# GERI_Gadget.net
KiCad netlist of a schematic drawn in EAGLE
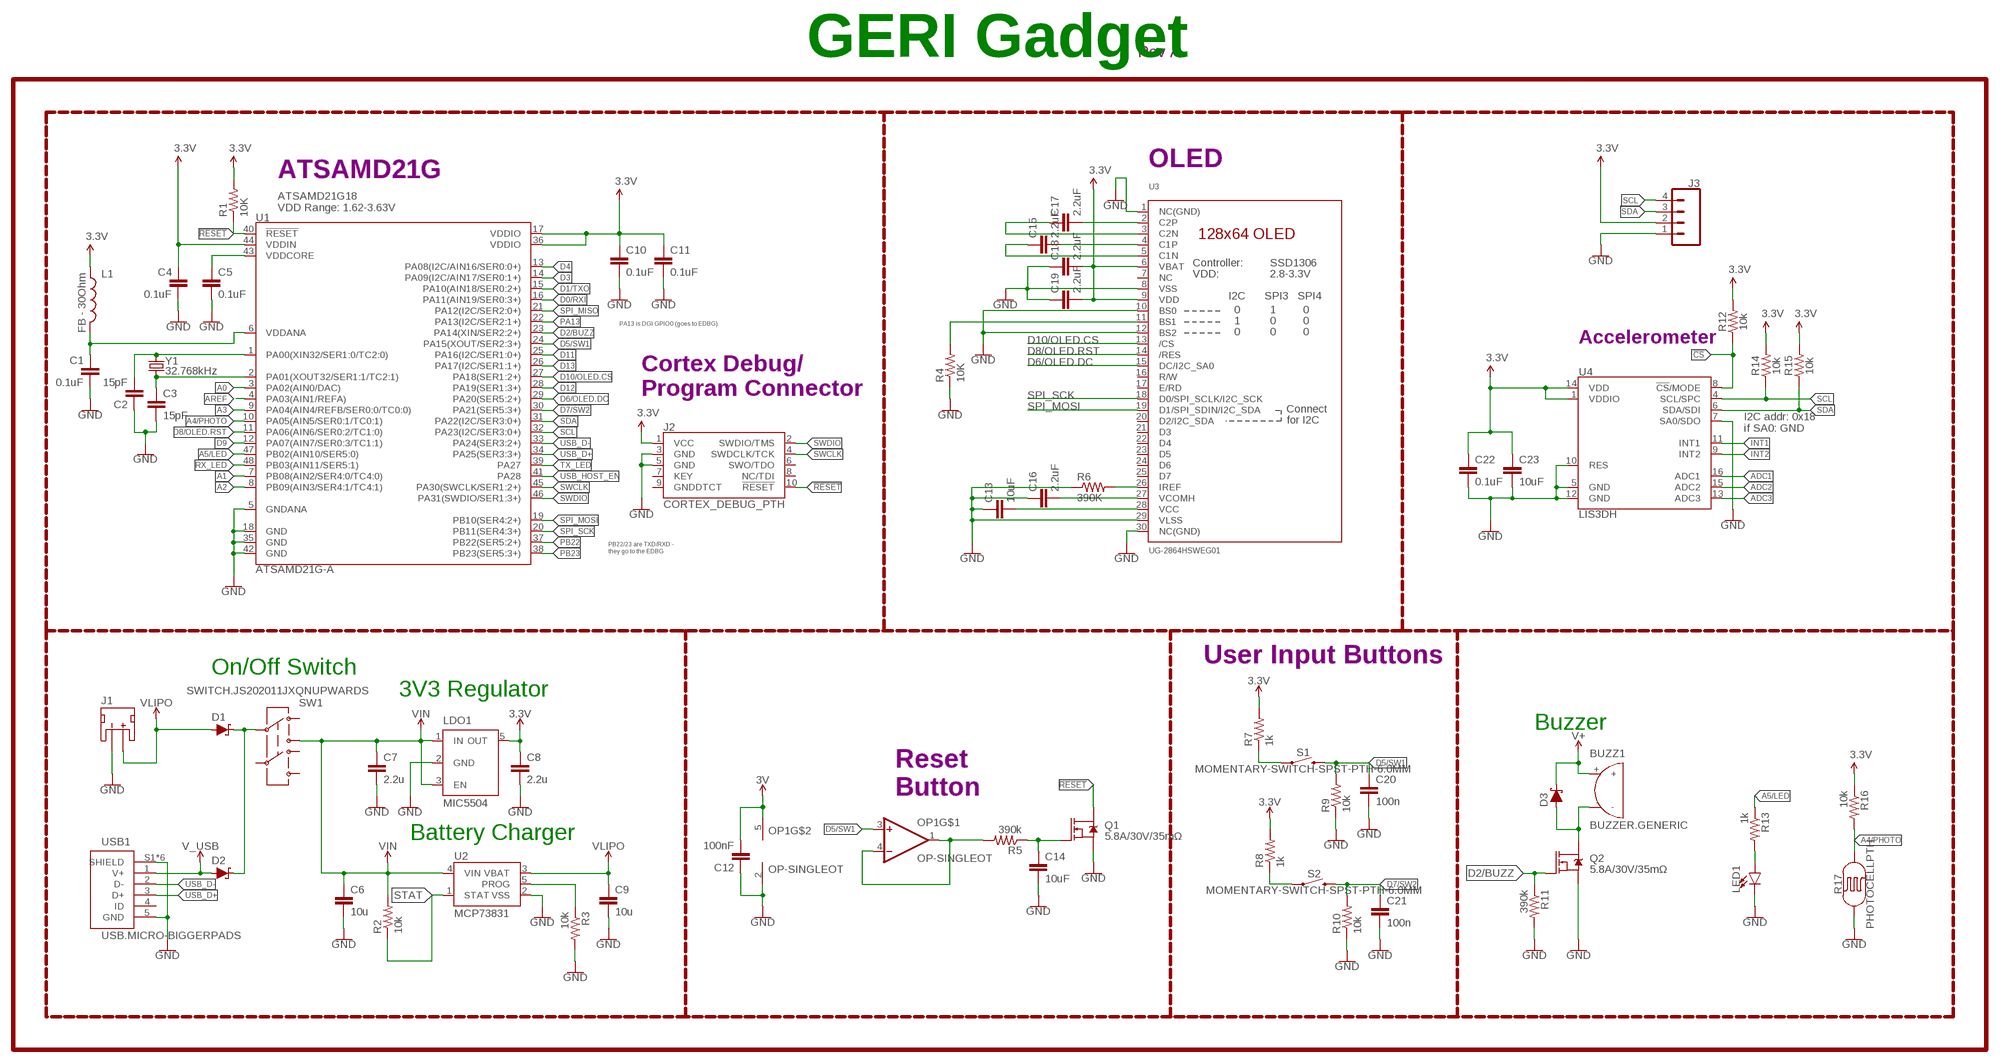
[diagram p0: schematic, sheet 1]

(export (version "E")
  (design (tool "Eeschema 10.0.6"))
  (components
    (comp (ref "BUZZ1")
      (value "BUZZER.GENERIC")
      (footprint "eagle-import:PIEZO-1")
      (libsource (lib "eagle-import") (part "BUZZER.GENERIC"))
    )
    (comp (ref "C1")
      (value "0.1uF")
      (footprint "eagle-import:C0402")
      (libsource (lib "eagle-import") (part "CAPACITOR0402"))
    )
    (comp (ref "C2")
      (value "15pF")
      (footprint "eagle-import:C0402")
      (libsource (lib "eagle-import") (part "CAPACITOR0402"))
    )
    (comp (ref "C3")
      (value "15pF")
      (footprint "eagle-import:C0402")
      (libsource (lib "eagle-import") (part "CAPACITOR0402"))
    )
    (comp (ref "C4")
      (value "0.1uF")
      (footprint "eagle-import:C0402")
      (libsource (lib "eagle-import") (part "CAPACITOR0402"))
    )
    (comp (ref "C5")
      (value "0.1uF")
      (footprint "eagle-import:C0402")
      (libsource (lib "eagle-import") (part "CAPACITOR0402"))
    )
    (comp (ref "C6")
      (value "10u")
      (footprint "eagle-import:C0603")
      (libsource (lib "eagle-import") (part "CAPACITOR0603"))
    )
    (comp (ref "C7")
      (value "2.2u")
      (footprint "eagle-import:C0603")
      (libsource (lib "eagle-import") (part "CAPACITOR0603"))
    )
    (comp (ref "C8")
      (value "2.2u")
      (footprint "eagle-import:C0603")
      (libsource (lib "eagle-import") (part "CAPACITOR0603"))
    )
    (comp (ref "C9")
      (value "10u")
      (footprint "eagle-import:C0603")
      (libsource (lib "eagle-import") (part "CAPACITOR0603"))
    )
    (comp (ref "C10")
      (value "0.1uF")
      (footprint "eagle-import:C0402")
      (libsource (lib "eagle-import") (part "CAPACITOR0402"))
    )
    (comp (ref "C11")
      (value "0.1uF")
      (footprint "eagle-import:C0402")
      (libsource (lib "eagle-import") (part "CAPACITOR0402"))
    )
    (comp (ref "C12")
      (value "100nF")
      (footprint "eagle-import:C0402")
      (libsource (lib "eagle-import") (part "CAPACITOR0402"))
    )
    (comp (ref "C13")
      (value "10uF")
      (footprint "eagle-import:C0603")
      (libsource (lib "eagle-import") (part "CAPACITOR0603"))
    )
    (comp (ref "C14")
      (value "10uF")
      (footprint "eagle-import:C0603")
      (libsource (lib "eagle-import") (part "CAPACITOR0603"))
    )
    (comp (ref "C15")
      (value "2.2uF")
      (footprint "eagle-import:C0603")
      (libsource (lib "eagle-import") (part "CAPACITOR0603"))
    )
    (comp (ref "C16")
      (value "2.2uF")
      (footprint "eagle-import:C0603")
      (libsource (lib "eagle-import") (part "CAPACITOR0603"))
    )
    (comp (ref "C17")
      (value "2.2uF")
      (footprint "eagle-import:C0603")
      (libsource (lib "eagle-import") (part "CAPACITOR0603"))
    )
    (comp (ref "C18")
      (value "2.2uF")
      (footprint "eagle-import:C0603")
      (libsource (lib "eagle-import") (part "CAPACITOR0603"))
    )
    (comp (ref "C19")
      (value "2.2uF")
      (footprint "eagle-import:C0603")
      (libsource (lib "eagle-import") (part "CAPACITOR0603"))
    )
    (comp (ref "C20")
      (value "100n")
      (footprint "eagle-import:C0402")
      (libsource (lib "eagle-import") (part "CAPACITOR0402"))
    )
    (comp (ref "C21")
      (value "100n")
      (footprint "eagle-import:C0402")
      (libsource (lib "eagle-import") (part "CAPACITOR0402"))
    )
    (comp (ref "C22")
      (value "0.1uF")
      (footprint "eagle-import:0402")
      (libsource (lib "eagle-import") (part "0.1UF-0402-16V-10%"))
    )
    (comp (ref "C23")
      (value "10uF")
      (footprint "eagle-import:0603")
      (libsource (lib "eagle-import") (part "10UF-0603-6.3V-20%"))
    )
    (comp (ref "D1")
      (value "SCHOTTKY-USC")
      (footprint "eagle-import:USC")
      (libsource (lib "eagle-import") (part "SCHOTTKY-USC"))
    )
    (comp (ref "D2")
      (value "SCHOTTKY-USC")
      (footprint "eagle-import:USC")
      (libsource (lib "eagle-import") (part "SCHOTTKY-USC"))
    )
    (comp (ref "D3")
      (value "SCHOTTKY-USC")
      (footprint "eagle-import:USC")
      (libsource (lib "eagle-import") (part "SCHOTTKY-USC"))
    )
    (comp (ref "J1")
      (value "JST_2MM_MALE")
      (footprint "eagle-import:JST-2-SMD")
      (libsource (lib "eagle-import") (part "JST_2MM_MALE"))
    )
    (comp (ref "J2")
      (value "CORTEX_DEBUG_PTH")
      (footprint "eagle-import:2X5-PTH-1.27MM")
      (libsource (lib "eagle-import") (part "CORTEX_DEBUG_PTH"))
    )
    (comp (ref "J3")
      (value "CONN_04")
      (footprint "eagle-import:1X04")
      (libsource (lib "eagle-import") (part "CONN_04"))
    )
    (comp (ref "L1")
      (value "FB - 30Ohm")
      (footprint "eagle-import:0603")
      (libsource (lib "eagle-import") (part "INDUCTOR0603"))
    )
    (comp (ref "LDO1")
      (value "MIC5504")
      (footprint "eagle-import:SOT23-5")
      (libsource (lib "eagle-import") (part "MIC5504"))
    )
    (comp (ref "LED1")
      (value "LED5MM")
      (footprint "eagle-import:LED_5MM")
      (libsource (lib "eagle-import") (part "LED5MM"))
    )
    (comp (ref "OP1")
      (value "OP-SINGLEOT")
      (footprint "eagle-import:SOT23-5")
      (libsource (lib "eagle-import") (part "OP-SINGLEOT"))
    )
    (comp (ref "Q1")
      (value "5.8A/30V/35mΩ")
      (footprint "eagle-import:SOT23-3")
      (libsource (lib "eagle-import") (part "NFET-AO3404A"))
    )
    (comp (ref "Q2")
      (value "5.8A/30V/35mΩ")
      (footprint "eagle-import:SOT23-3")
      (libsource (lib "eagle-import") (part "NFET-AO3404A"))
    )
    (comp (ref "R1")
      (value "10K")
      (footprint "eagle-import:R0402-BIGGER")
      (libsource (lib "eagle-import") (part "RESISTOR0402-BIGGER"))
    )
    (comp (ref "R2")
      (value "10k")
      (footprint "eagle-import:R0402-BIGGER")
      (libsource (lib "eagle-import") (part "RESISTOR0402-BIGGER"))
    )
    (comp (ref "R3")
      (value "10k")
      (footprint "eagle-import:R0402-BIGGER")
      (libsource (lib "eagle-import") (part "RESISTOR0402-BIGGER"))
    )
    (comp (ref "R4")
      (value "10K")
      (footprint "eagle-import:R0402-BIGGER")
      (libsource (lib "eagle-import") (part "RESISTOR0402-BIGGER"))
    )
    (comp (ref "R5")
      (value "390k")
      (footprint "eagle-import:R0402-BIGGER")
      (libsource (lib "eagle-import") (part "RESISTOR0402-BIGGER"))
    )
    (comp (ref "R6")
      (value "390K")
      (footprint "eagle-import:R0402-BIGGER")
      (libsource (lib "eagle-import") (part "RESISTOR0402-BIGGER"))
    )
    (comp (ref "R7")
      (value "1k")
      (footprint "eagle-import:R0402-BIGGER")
      (libsource (lib "eagle-import") (part "RESISTOR0402-BIGGER"))
    )
    (comp (ref "R8")
      (value "1k")
      (footprint "eagle-import:R0402-BIGGER")
      (libsource (lib "eagle-import") (part "RESISTOR0402-BIGGER"))
    )
    (comp (ref "R9")
      (value "10k")
      (footprint "eagle-import:R0402-BIGGER")
      (libsource (lib "eagle-import") (part "RESISTOR0402-BIGGER"))
    )
    (comp (ref "R10")
      (value "10k")
      (footprint "eagle-import:R0402-BIGGER")
      (libsource (lib "eagle-import") (part "RESISTOR0402-BIGGER"))
    )
    (comp (ref "R11")
      (value "390k")
      (footprint "eagle-import:R0402-BIGGER")
      (libsource (lib "eagle-import") (part "RESISTOR0402-BIGGER"))
    )
    (comp (ref "R12")
      (value "10k")
      (footprint "eagle-import:0402")
      (libsource (lib "eagle-import") (part "RESISTOR0402"))
    )
    (comp (ref "R13")
      (value "1k")
      (footprint "eagle-import:R0402-BIGGER")
      (libsource (lib "eagle-import") (part "RESISTOR0402-BIGGER"))
    )
    (comp (ref "R14")
      (value "10k")
      (footprint "eagle-import:0402")
      (libsource (lib "eagle-import") (part "RESISTOR0402"))
    )
    (comp (ref "R15")
      (value "10k")
      (footprint "eagle-import:0402")
      (libsource (lib "eagle-import") (part "RESISTOR0402"))
    )
    (comp (ref "R16")
      (value "10k")
      (footprint "eagle-import:R0402-BIGGER")
      (libsource (lib "eagle-import") (part "RESISTOR0402-BIGGER"))
    )
    (comp (ref "R17")
      (value "PHOTOCELLPTH")
      (footprint "eagle-import:PHOTOCELL")
      (libsource (lib "eagle-import") (part "PHOTOCELLPTH"))
    )
    (comp (ref "REV1")
      (value "REVISION.A")
      (footprint "eagle-import:REV.A")
      (libsource (lib "eagle-import") (part "REVISION.A"))
    )
    (comp (ref "S1")
      (value "MOMENTARY-SWITCH-SPST-PTH-6.0MM")
      (footprint "eagle-import:TACTILE_SWITCH_PTH_6.0MM")
      (libsource (lib "eagle-import") (part "MOMENTARY-SWITCH-SPST-PTH-6.0MM"))
    )
    (comp (ref "S2")
      (value "MOMENTARY-SWITCH-SPST-PTH-6.0MM")
      (footprint "eagle-import:TACTILE_SWITCH_PTH_6.0MM")
      (libsource (lib "eagle-import") (part "MOMENTARY-SWITCH-SPST-PTH-6.0MM"))
    )
    (comp (ref "SW1")
      (value "SWITCH.JS202011JXQNUPWARDS")
      (footprint "eagle-import:SWITCH.00")
      (libsource (lib "eagle-import") (part "SWITCH.JS202011JXQNUPWARDS"))
    )
    (comp (ref "U1")
      (value "ATSAMD21G-A")
      (footprint "eagle-import:TQFP-48")
      (libsource (lib "eagle-import") (part "ATSAMD21G-A"))
    )
    (comp (ref "U2")
      (value "MCP73831")
      (footprint "eagle-import:SOT23-5")
      (libsource (lib "eagle-import") (part "MCP73831"))
    )
    (comp (ref "U3")
      (value "UG-2864HSWEG01")
      (footprint "eagle-import:UG-2864HSWEG01_0.96IN_NO-WRAPAROUND")
      (libsource (lib "eagle-import") (part "DISP_OLED_UG-2864HSWEG01-NO-WRAPAROUND"))
    )
    (comp (ref "U4")
      (value "LIS3DH")
      (footprint "eagle-import:LGA-16-3X3")
      (libsource (lib "eagle-import") (part "LIS3DH"))
    )
    (comp (ref "USB1")
      (value "USB.MICRO-BIGGERPADS")
      (footprint "eagle-import:USB-MICRO-01.BIGGERPADS")
      (libsource (lib "eagle-import") (part "USB.MICRO-BIGGERPADS"))
    )
    (comp (ref "Y1")
      (value "32.768kHz")
      (footprint "eagle-import:CRYSTAL-SMD-3.2X1.5MM")
      (libsource (lib "eagle-import") (part "CRYSTAL3.2X1.5MM"))
    )
  )
  (nets
    (net (code "1") (name "/~{CS}") (class "Default")
      (node (ref "R12") (pin "1") (pinfunction "1_1") (pintype "passive"))
      (node (ref "U4") (pin "8") (pinfunction "~{CS}/MODE_8") (pintype "bidirectional"))
    )
    (net (code "2") (name "/~{RESET}") (class "Default")
      (node (ref "J2") (pin "10") (pinfunction "~{RESET}_10") (pintype "bidirectional"))
      (node (ref "Q1") (pin "3") (pinfunction "D_3") (pintype "bidirectional"))
      (node (ref "R1") (pin "1") (pinfunction "1_1") (pintype "passive"))
      (node (ref "U1") (pin "40") (pinfunction "~{RESET}_40") (pintype "bidirectional"))
    )
    (net (code "3") (name "3.3V") (class "Default")
      (node (ref "C10") (pin "1") (pinfunction "1_1") (pintype "passive"))
      (node (ref "C11") (pin "1") (pinfunction "1_1") (pintype "passive"))
      (node (ref "C18") (pin "2") (pinfunction "2_2") (pintype "passive"))
      (node (ref "C19") (pin "2") (pinfunction "2_2") (pintype "passive"))
      (node (ref "C22") (pin "1") (pinfunction "1_1") (pintype "passive"))
      (node (ref "C23") (pin "1") (pinfunction "1_1") (pintype "passive"))
      (node (ref "C4") (pin "1") (pinfunction "1_1") (pintype "passive"))
      (node (ref "C8") (pin "1") (pinfunction "1_1") (pintype "passive"))
      (node (ref "J2") (pin "1") (pinfunction "VCC_1") (pintype "bidirectional"))
      (node (ref "J3") (pin "2") (pinfunction "2_2") (pintype "passive"))
      (node (ref "L1") (pin "1") (pinfunction "1_1") (pintype "passive"))
      (node (ref "LDO1") (pin "5") (pinfunction "OUT_5") (pintype "bidirectional"))
      (node (ref "R1") (pin "2") (pinfunction "2_2") (pintype "passive"))
      (node (ref "R12") (pin "2") (pinfunction "2_2") (pintype "passive"))
      (node (ref "R14") (pin "2") (pinfunction "2_2") (pintype "passive"))
      (node (ref "R15") (pin "2") (pinfunction "2_2") (pintype "passive"))
      (node (ref "R16") (pin "1") (pinfunction "1_1") (pintype "passive"))
      (node (ref "R7") (pin "2") (pinfunction "2_2") (pintype "passive"))
      (node (ref "R8") (pin "2") (pinfunction "2_2") (pintype "passive"))
      (node (ref "U1") (pin "17") (pinfunction "VDDIO_17") (pintype "bidirectional"))
      (node (ref "U1") (pin "36") (pinfunction "VDDIO_36") (pintype "bidirectional"))
      (node (ref "U1") (pin "44") (pinfunction "VDDIN_44") (pintype "bidirectional"))
      (node (ref "U3") (pin "6") (pinfunction "VBAT_6") (pintype "input"))
      (node (ref "U3") (pin "9") (pinfunction "VDD_9") (pintype "power_in"))
      (node (ref "U4") (pin "1") (pinfunction "VDDIO_1") (pintype "bidirectional"))
      (node (ref "U4") (pin "14") (pinfunction "VDD_14") (pintype "bidirectional"))
    )
    (net (code "4") (name "3V") (class "Default")
      (node (ref "C12") (pin "2") (pinfunction "2_2") (pintype "passive"))
      (node (ref "OP1") (pin "5") (pinfunction "V+_5") (pintype "power_in"))
    )
    (net (code "5") (name "A0") (class "Default")
      (node (ref "U1") (pin "3") (pinfunction "PA02(AIN0/DAC)_3") (pintype "bidirectional"))
    )
    (net (code "6") (name "A1") (class "Default")
      (node (ref "U1") (pin "7") (pinfunction "PB08(AIN2/SER4:0/TC4:0)_7") (pintype "bidirectional"))
    )
    (net (code "7") (name "A2") (class "Default")
      (node (ref "U1") (pin "8") (pinfunction "PB09(AIN3/SER4:1/TC4:1)_8") (pintype "bidirectional"))
    )
    (net (code "8") (name "A3") (class "Default")
      (node (ref "U1") (pin "9") (pinfunction "PA04(AIN4/REFB/SER0:0/TC0:0)_9") (pintype "bidirectional"))
    )
    (net (code "9") (name "A4{slash}PHOTO") (class "Default")
      (node (ref "R16") (pin "2") (pinfunction "2_2") (pintype "passive"))
      (node (ref "R17") (pin "2") (pinfunction "P$2_2") (pintype "bidirectional"))
      (node (ref "U1") (pin "10") (pinfunction "PA05(AIN5/SER0:1/TC0:1)_10") (pintype "bidirectional"))
    )
    (net (code "10") (name "A5{slash}LED") (class "Default")
      (node (ref "R13") (pin "1") (pinfunction "1_1") (pintype "passive"))
      (node (ref "U1") (pin "47") (pinfunction "PB02(AIN10/SER5:0)_47") (pintype "bidirectional"))
    )
    (net (code "11") (name "ADC1") (class "Default")
      (node (ref "U4") (pin "16") (pinfunction "ADC1_16") (pintype "bidirectional"))
    )
    (net (code "12") (name "ADC2") (class "Default")
      (node (ref "U4") (pin "15") (pinfunction "ADC2_15") (pintype "bidirectional"))
    )
    (net (code "13") (name "ADC3") (class "Default")
      (node (ref "U4") (pin "13") (pinfunction "ADC3_13") (pintype "bidirectional"))
    )
    (net (code "14") (name "AREF") (class "Default")
      (node (ref "U1") (pin "4") (pinfunction "PA03(AIN1/REFA)_4") (pintype "bidirectional"))
    )
    (net (code "15") (name "D0{slash}RXI") (class "Default")
      (node (ref "U1") (pin "16") (pinfunction "PA11(AIN19/SER0:3+)_16") (pintype "bidirectional"))
    )
    (net (code "16") (name "D1{slash}TXO") (class "Default")
      (node (ref "U1") (pin "15") (pinfunction "PA10(AIN18/SER0:2+)_15") (pintype "bidirectional"))
    )
    (net (code "17") (name "D2{slash}BUZZ") (class "Default")
      (node (ref "Q2") (pin "1") (pinfunction "G_1") (pintype "bidirectional"))
      (node (ref "R11") (pin "1") (pinfunction "1_1") (pintype "passive"))
      (node (ref "U1") (pin "23") (pinfunction "PA14(XIN/SER2:2+)_23") (pintype "bidirectional"))
    )
    (net (code "18") (name "D3") (class "Default")
      (node (ref "U1") (pin "14") (pinfunction "PA09(I2C/AIN17/SER0:1+)_14") (pintype "bidirectional"))
    )
    (net (code "19") (name "D4") (class "Default")
      (node (ref "U1") (pin "13") (pinfunction "PA08(I2C/AIN16/SER0:0+)_13") (pintype "bidirectional"))
    )
    (net (code "20") (name "D5{slash}SW1") (class "Default")
      (node (ref "C20") (pin "1") (pinfunction "1_1") (pintype "passive"))
      (node (ref "OP1") (pin "3") (pinfunction "+IN_3") (pintype "input"))
      (node (ref "R9") (pin "2") (pinfunction "2_2") (pintype "passive"))
      (node (ref "S1") (pin "3") (pinfunction "2_3") (pintype "passive"))
      (node (ref "U1") (pin "24") (pinfunction "PA15(XOUT/SER2:3+)_24") (pintype "bidirectional"))
    )
    (net (code "21") (name "D6{slash}OLED.DC") (class "Default")
      (node (ref "U1") (pin "29") (pinfunction "PA20(SER5:2+)_29") (pintype "bidirectional"))
      (node (ref "U3") (pin "15") (pinfunction "DC/I2C_SA0_15") (pintype "input"))
    )
    (net (code "22") (name "D7{slash}SW2") (class "Default")
      (node (ref "C21") (pin "1") (pinfunction "1_1") (pintype "passive"))
      (node (ref "R10") (pin "2") (pinfunction "2_2") (pintype "passive"))
      (node (ref "S2") (pin "3") (pinfunction "2_3") (pintype "passive"))
      (node (ref "U1") (pin "30") (pinfunction "PA21(SER5:3+)_30") (pintype "bidirectional"))
    )
    (net (code "23") (name "D8{slash}OLED.RST") (class "Default")
      (node (ref "U1") (pin "11") (pinfunction "PA06(AIN6/SER0:2/TC1:0)_11") (pintype "bidirectional"))
      (node (ref "U3") (pin "14") (pinfunction "/RES_14") (pintype "input"))
    )
    (net (code "24") (name "D9") (class "Default")
      (node (ref "U1") (pin "12") (pinfunction "PA07(AIN7/SER0:3/TC1:1)_12") (pintype "bidirectional"))
    )
    (net (code "25") (name "D10{slash}OLED.CS") (class "Default")
      (node (ref "U1") (pin "27") (pinfunction "PA18(SER1:2+)_27") (pintype "bidirectional"))
      (node (ref "U3") (pin "13") (pinfunction "/CS_13") (pintype "input"))
    )
    (net (code "26") (name "D11") (class "Default")
      (node (ref "U1") (pin "25") (pinfunction "PA16(I2C/SER1:0+)_25") (pintype "bidirectional"))
    )
    (net (code "27") (name "D12") (class "Default")
      (node (ref "U1") (pin "28") (pinfunction "PA19(SER1:3+)_28") (pintype "bidirectional"))
    )
    (net (code "28") (name "D13") (class "Default")
      (node (ref "U1") (pin "26") (pinfunction "PA17(I2C/SER1:1+)_26") (pintype "bidirectional"))
    )
    (net (code "29") (name "GND") (class "Default")
      (node (ref "C1") (pin "2") (pinfunction "2_2") (pintype "passive"))
      (node (ref "C10") (pin "2") (pinfunction "2_2") (pintype "passive"))
      (node (ref "C11") (pin "2") (pinfunction "2_2") (pintype "passive"))
      (node (ref "C12") (pin "1") (pinfunction "1_1") (pintype "passive"))
      (node (ref "C13") (pin "1") (pinfunction "1_1") (pintype "passive"))
      (node (ref "C14") (pin "2") (pinfunction "2_2") (pintype "passive"))
      (node (ref "C16") (pin "1") (pinfunction "1_1") (pintype "passive"))
      (node (ref "C18") (pin "1") (pinfunction "1_1") (pintype "passive"))
      (node (ref "C19") (pin "1") (pinfunction "1_1") (pintype "passive"))
      (node (ref "C2") (pin "1") (pinfunction "1_1") (pintype "passive"))
      (node (ref "C20") (pin "2") (pinfunction "2_2") (pintype "passive"))
      (node (ref "C21") (pin "2") (pinfunction "2_2") (pintype "passive"))
      (node (ref "C22") (pin "2") (pinfunction "2_2") (pintype "passive"))
      (node (ref "C23") (pin "2") (pinfunction "2_2") (pintype "passive"))
      (node (ref "C3") (pin "2") (pinfunction "2_2") (pintype "passive"))
      (node (ref "C4") (pin "2") (pinfunction "2_2") (pintype "passive"))
      (node (ref "C5") (pin "2") (pinfunction "2_2") (pintype "passive"))
      (node (ref "C6") (pin "2") (pinfunction "2_2") (pintype "passive"))
      (node (ref "C7") (pin "2") (pinfunction "2_2") (pintype "passive"))
      (node (ref "C8") (pin "2") (pinfunction "2_2") (pintype "passive"))
      (node (ref "C9") (pin "2") (pinfunction "2_2") (pintype "passive"))
      (node (ref "J1") (pin "1") (pinfunction "-_1") (pintype "bidirectional"))
      (node (ref "J2") (pin "3") (pinfunction "GND_3") (pintype "bidirectional"))
      (node (ref "J2") (pin "5") (pinfunction "GND_5") (pintype "bidirectional"))
      (node (ref "J3") (pin "1") (pinfunction "1_1") (pintype "passive"))
      (node (ref "LDO1") (pin "2") (pinfunction "GND_2") (pintype "bidirectional"))
      (node (ref "LED1") (pin "K") (pinfunction "C_K") (pintype "passive"))
      (node (ref "OP1") (pin "2") (pinfunction "V-_2") (pintype "power_in"))
      (node (ref "Q1") (pin "2") (pinfunction "S_2") (pintype "bidirectional"))
      (node (ref "Q2") (pin "2") (pinfunction "S_2") (pintype "bidirectional"))
      (node (ref "R10") (pin "1") (pinfunction "1_1") (pintype "passive"))
      (node (ref "R11") (pin "2") (pinfunction "2_2") (pintype "passive"))
      (node (ref "R17") (pin "1") (pinfunction "P$1_1") (pintype "bidirectional"))
      (node (ref "R3") (pin "2") (pinfunction "2_2") (pintype "passive"))
      (node (ref "R4") (pin "1") (pinfunction "1_1") (pintype "passive"))
      (node (ref "R6") (pin "1") (pinfunction "1_1") (pintype "passive"))
      (node (ref "R9") (pin "1") (pinfunction "1_1") (pintype "passive"))
      (node (ref "U1") (pin "18") (pinfunction "GND_18") (pintype "bidirectional"))
      (node (ref "U1") (pin "35") (pinfunction "GND_35") (pintype "bidirectional"))
      (node (ref "U1") (pin "42") (pinfunction "GND_42") (pintype "bidirectional"))
      (node (ref "U1") (pin "5") (pinfunction "GNDANA_5") (pintype "bidirectional"))
      (node (ref "U2") (pin "2") (pinfunction "VSS_2") (pintype "power_in"))
      (node (ref "U3") (pin "1") (pinfunction "NC(GND)_1") (pintype "input"))
      (node (ref "U3") (pin "10") (pinfunction "BS0_10") (pintype "input"))
      (node (ref "U3") (pin "12") (pinfunction "BS2_12") (pintype "input"))
      (node (ref "U3") (pin "29") (pinfunction "VLSS_29") (pintype "power_in"))
      (node (ref "U3") (pin "30") (pinfunction "NC(GND)_30") (pintype "input"))
      (node (ref "U3") (pin "8") (pinfunction "VSS_8") (pintype "power_in"))
      (node (ref "U4") (pin "10") (pinfunction "RES_10") (pintype "bidirectional"))
      (node (ref "U4") (pin "12") (pinfunction "GND_12") (pintype "bidirectional"))
      (node (ref "U4") (pin "5") (pinfunction "GND_5") (pintype "bidirectional"))
      (node (ref "U4") (pin "7") (pinfunction "SA0/SDO_7") (pintype "bidirectional"))
      (node (ref "USB1") (pin "5") (pinfunction "GND_5") (pintype "bidirectional"))
      (node (ref "USB1") (pin "S1") (pinfunction "SHIELD_S1") (pintype "bidirectional"))
      (node (ref "USB1") (pin "S2") (pinfunction "SHIELD_S2") (pintype "bidirectional"))
      (node (ref "USB1") (pin "S3") (pinfunction "SHIELD_S3") (pintype "bidirectional"))
      (node (ref "USB1") (pin "S4") (pinfunction "SHIELD_S4") (pintype "bidirectional"))
      (node (ref "USB1") (pin "S5") (pinfunction "SHIELD_S5") (pintype "bidirectional"))
      (node (ref "USB1") (pin "S6") (pinfunction "SHIELD_S6") (pintype "bidirectional"))
    )
    (net (code "30") (name "INT1") (class "Default")
      (node (ref "U4") (pin "11") (pinfunction "INT1_11") (pintype "bidirectional"))
    )
    (net (code "31") (name "INT2") (class "Default")
      (node (ref "U4") (pin "9") (pinfunction "INT2_9") (pintype "bidirectional"))
    )
    (net (code "32") (name "Net-(D1-C)") (class "Default")
      (node (ref "D1") (pin "-") (pinfunction "C_-") (pintype "passive"))
      (node (ref "D2") (pin "-") (pinfunction "C_-") (pintype "passive"))
      (node (ref "SW1") (pin "2") (pinfunction "2_2") (pintype "bidirectional"))
    )
    (net (code "33") (name "Net-(D3-A)") (class "Default")
      (node (ref "BUZZ1") (pin "-") (pinfunction "-_-") (pintype "bidirectional"))
      (node (ref "D3") (pin "+") (pinfunction "A_+") (pintype "passive"))
      (node (ref "Q2") (pin "3") (pinfunction "D_3") (pintype "bidirectional"))
    )
    (net (code "34") (name "Net-(LED1-PadA)") (class "Default")
      (node (ref "LED1") (pin "A") (pinfunction "A_A") (pintype "passive"))
      (node (ref "R13") (pin "2") (pinfunction "2_2") (pintype "passive"))
    )
    (net (code "35") (name "Net-(OP1A--IN)") (class "Default")
      (node (ref "OP1") (pin "1") (pinfunction "OUT_1") (pintype "output"))
      (node (ref "OP1") (pin "4") (pinfunction "-IN_4") (pintype "input"))
      (node (ref "R5") (pin "2") (pinfunction "2_2") (pintype "passive"))
    )
    (net (code "36") (name "Net-(Q1-G)") (class "Default")
      (node (ref "C14") (pin "1") (pinfunction "1_1") (pintype "passive"))
      (node (ref "Q1") (pin "1") (pinfunction "G_1") (pintype "bidirectional"))
      (node (ref "R5") (pin "1") (pinfunction "1_1") (pintype "passive"))
    )
    (net (code "37") (name "Net-(R7-Pad1)") (class "Default")
      (node (ref "R7") (pin "1") (pinfunction "1_1") (pintype "passive"))
      (node (ref "S1") (pin "1") (pinfunction "1_1") (pintype "passive"))
    )
    (net (code "38") (name "Net-(R8-Pad1)") (class "Default")
      (node (ref "R8") (pin "1") (pinfunction "1_1") (pintype "passive"))
      (node (ref "S2") (pin "1") (pinfunction "1_1") (pintype "passive"))
    )
    (net (code "39") (name "Net-(U1-PA00(XIN32{slash}SER1:0{slash}TC2:0))") (class "Default")
      (node (ref "C2") (pin "2") (pinfunction "2_2") (pintype "passive"))
      (node (ref "U1") (pin "1") (pinfunction "PA00(XIN32/SER1:0/TC2:0)_1") (pintype "bidirectional"))
      (node (ref "Y1") (pin "P$2") (pinfunction "2_P$2") (pintype "passive"))
    )
    (net (code "40") (name "Net-(U1-PA01(XOUT32{slash}SER1:1{slash}TC2:1))") (class "Default")
      (node (ref "C3") (pin "1") (pinfunction "1_1") (pintype "passive"))
      (node (ref "U1") (pin "2") (pinfunction "PA01(XOUT32/SER1:1/TC2:1)_2") (pintype "bidirectional"))
      (node (ref "Y1") (pin "P$1") (pinfunction "1_P$1") (pintype "passive"))
    )
    (net (code "41") (name "Net-(U1-VDDANA)") (class "Default")
      (node (ref "C1") (pin "1") (pinfunction "1_1") (pintype "passive"))
      (node (ref "L1") (pin "2") (pinfunction "2_2") (pintype "passive"))
      (node (ref "U1") (pin "6") (pinfunction "VDDANA_6") (pintype "bidirectional"))
    )
    (net (code "42") (name "Net-(U1-VDDCORE)") (class "Default")
      (node (ref "C5") (pin "1") (pinfunction "1_1") (pintype "passive"))
      (node (ref "U1") (pin "43") (pinfunction "VDDCORE_43") (pintype "bidirectional"))
    )
    (net (code "43") (name "Net-(U2-PROG)") (class "Default")
      (node (ref "R3") (pin "1") (pinfunction "1_1") (pintype "passive"))
      (node (ref "U2") (pin "5") (pinfunction "PROG_5") (pintype "input"))
    )
    (net (code "44") (name "Net-(U3-BS1)") (class "Default")
      (node (ref "R4") (pin "2") (pinfunction "2_2") (pintype "passive"))
      (node (ref "U3") (pin "11") (pinfunction "BS1_11") (pintype "input"))
    )
    (net (code "45") (name "Net-(U3-C1N)") (class "Default")
      (node (ref "C15") (pin "1") (pinfunction "1_1") (pintype "passive"))
      (node (ref "U3") (pin "5") (pinfunction "C1N_5") (pintype "input"))
    )
    (net (code "46") (name "Net-(U3-C1P)") (class "Default")
      (node (ref "C15") (pin "2") (pinfunction "2_2") (pintype "passive"))
      (node (ref "U3") (pin "4") (pinfunction "C1P_4") (pintype "input"))
    )
    (net (code "47") (name "Net-(U3-C2N)") (class "Default")
      (node (ref "C17") (pin "1") (pinfunction "1_1") (pintype "passive"))
      (node (ref "U3") (pin "3") (pinfunction "C2N_3") (pintype "input"))
    )
    (net (code "48") (name "Net-(U3-C2P)") (class "Default")
      (node (ref "C17") (pin "2") (pinfunction "2_2") (pintype "passive"))
      (node (ref "U3") (pin "2") (pinfunction "C2P_2") (pintype "input"))
    )
    (net (code "49") (name "Net-(U3-IREF)") (class "Default")
      (node (ref "R6") (pin "2") (pinfunction "2_2") (pintype "passive"))
      (node (ref "U3") (pin "26") (pinfunction "IREF_26") (pintype "input"))
    )
    (net (code "50") (name "Net-(U3-VCC)") (class "Default")
      (node (ref "C13") (pin "2") (pinfunction "2_2") (pintype "passive"))
      (node (ref "U3") (pin "28") (pinfunction "VCC_28") (pintype "power_in"))
    )
    (net (code "51") (name "Net-(U3-VCOMH)") (class "Default")
      (node (ref "C16") (pin "2") (pinfunction "2_2") (pintype "passive"))
      (node (ref "U3") (pin "27") (pinfunction "VCOMH_27") (pintype "output"))
    )
    (net (code "52") (name "PA13") (class "Default")
      (node (ref "U1") (pin "22") (pinfunction "PA13(I2C/SER2:1+)_22") (pintype "bidirectional"))
    )
    (net (code "53") (name "PB22") (class "Default")
      (node (ref "U1") (pin "37") (pinfunction "PB22(SER5:2+)_37") (pintype "bidirectional"))
    )
    (net (code "54") (name "PB23") (class "Default")
      (node (ref "U1") (pin "38") (pinfunction "PB23(SER5:3+)_38") (pintype "bidirectional"))
    )
    (net (code "55") (name "RX_LED") (class "Default")
      (node (ref "U1") (pin "48") (pinfunction "PB03(AIN11/SER5:1)_48") (pintype "bidirectional"))
    )
    (net (code "56") (name "SCL") (class "Default")
      (node (ref "J3") (pin "4") (pinfunction "4_4") (pintype "passive"))
      (node (ref "R14") (pin "1") (pinfunction "1_1") (pintype "passive"))
      (node (ref "U1") (pin "32") (pinfunction "PA23(I2C/SER3:0+)_32") (pintype "bidirectional"))
      (node (ref "U4") (pin "4") (pinfunction "SCL/SPC_4") (pintype "bidirectional"))
    )
    (net (code "57") (name "SDA") (class "Default")
      (node (ref "J3") (pin "3") (pinfunction "3_3") (pintype "passive"))
      (node (ref "R15") (pin "1") (pinfunction "1_1") (pintype "passive"))
      (node (ref "U1") (pin "31") (pinfunction "PA22(I2C/SER3:0+)_31") (pintype "bidirectional"))
      (node (ref "U4") (pin "6") (pinfunction "SDA/SDI_6") (pintype "bidirectional"))
    )
    (net (code "58") (name "SPI_MISO") (class "Default")
      (node (ref "U1") (pin "21") (pinfunction "PA12(I2C/SER2:0+)_21") (pintype "bidirectional"))
    )
    (net (code "59") (name "SPI_MOSI") (class "Default")
      (node (ref "U1") (pin "19") (pinfunction "PB10(SER4:2+)_19") (pintype "bidirectional"))
      (node (ref "U3") (pin "19") (pinfunction "D1/SPI_SDIN/I2C_SDA_19") (pintype "bidirectional"))
    )
    (net (code "60") (name "SPI_SCK") (class "Default")
      (node (ref "U1") (pin "20") (pinfunction "PB11(SER4:3+)_20") (pintype "bidirectional"))
      (node (ref "U3") (pin "18") (pinfunction "D0/SPI_SCLK/I2C_SCK_18") (pintype "bidirectional"))
    )
    (net (code "61") (name "STAT") (class "Default")
      (node (ref "R2") (pin "1") (pinfunction "1_1") (pintype "passive"))
      (node (ref "U2") (pin "1") (pinfunction "STAT_1") (pintype "output"))
    )
    (net (code "62") (name "SWCLK") (class "Default")
      (node (ref "J2") (pin "4") (pinfunction "SWDCLK/TCK_4") (pintype "bidirectional"))
      (node (ref "U1") (pin "45") (pinfunction "PA30(SWCLK/SER1:2+)_45") (pintype "bidirectional"))
    )
    (net (code "63") (name "SWDIO") (class "Default")
      (node (ref "J2") (pin "2") (pinfunction "SWDIO/TMS_2") (pintype "bidirectional"))
      (node (ref "U1") (pin "46") (pinfunction "PA31(SWDIO/SER1:3+)_46") (pintype "bidirectional"))
    )
    (net (code "64") (name "TX_LED") (class "Default")
      (node (ref "U1") (pin "39") (pinfunction "PA27_39") (pintype "bidirectional"))
    )
    (net (code "65") (name "USB_D+") (class "Default")
      (node (ref "U1") (pin "34") (pinfunction "PA25(SER3:3+)_34") (pintype "bidirectional"))
      (node (ref "USB1") (pin "3") (pinfunction "D+_3") (pintype "bidirectional"))
    )
    (net (code "66") (name "USB_D-") (class "Default")
      (node (ref "U1") (pin "33") (pinfunction "PA24(SER3:2+)_33") (pintype "bidirectional"))
      (node (ref "USB1") (pin "2") (pinfunction "D-_2") (pintype "bidirectional"))
    )
    (net (code "67") (name "USB_HOST_EN") (class "Default")
      (node (ref "U1") (pin "41") (pinfunction "PA28_41") (pintype "bidirectional"))
    )
    (net (code "68") (name "V+") (class "Default")
      (node (ref "BUZZ1") (pin "+") (pinfunction "+_+") (pintype "bidirectional"))
      (node (ref "D3") (pin "-") (pinfunction "C_-") (pintype "passive"))
    )
    (net (code "69") (name "VIN") (class "Default")
      (node (ref "C6") (pin "1") (pinfunction "1_1") (pintype "passive"))
      (node (ref "C7") (pin "1") (pinfunction "1_1") (pintype "passive"))
      (node (ref "LDO1") (pin "1") (pinfunction "IN_1") (pintype "bidirectional"))
      (node (ref "LDO1") (pin "3") (pinfunction "EN_3") (pintype "bidirectional"))
      (node (ref "R2") (pin "2") (pinfunction "2_2") (pintype "passive"))
      (node (ref "SW1") (pin "3") (pinfunction "3_3") (pintype "bidirectional"))
      (node (ref "U2") (pin "4") (pinfunction "VIN_4") (pintype "power_in"))
    )
    (net (code "70") (name "VLIPO") (class "Default")
      (node (ref "C9") (pin "1") (pinfunction "1_1") (pintype "passive"))
      (node (ref "D1") (pin "+") (pinfunction "A_+") (pintype "passive"))
      (node (ref "J1") (pin "2") (pinfunction "+_2") (pintype "bidirectional"))
      (node (ref "U2") (pin "3") (pinfunction "VBAT_3") (pintype "power_in"))
    )
    (net (code "71") (name "V_USB") (class "Default")
      (node (ref "D2") (pin "+") (pinfunction "A_+") (pintype "passive"))
      (node (ref "USB1") (pin "1") (pinfunction "V+_1") (pintype "bidirectional"))
    )
    (net (code "72") (name "unconnected-(J1-PAD1-PadNC1)") (class "Default")
      (node (ref "J1") (pin "NC1") (pinfunction "PAD1_NC1") (pintype "bidirectional"))
    )
    (net (code "73") (name "unconnected-(J1-PAD2-PadNC2)") (class "Default")
      (node (ref "J1") (pin "NC2") (pinfunction "PAD2_NC2") (pintype "bidirectional"))
    )
    (net (code "74") (name "unconnected-(J2-GNDDTCT-Pad9)") (class "Default")
      (node (ref "J2") (pin "9") (pinfunction "GNDDTCT_9") (pintype "bidirectional"))
    )
    (net (code "75") (name "unconnected-(J2-KEY-Pad7)") (class "Default")
      (node (ref "J2") (pin "7") (pinfunction "KEY_7") (pintype "bidirectional"))
    )
    (net (code "76") (name "unconnected-(J2-NC{slash}TDI-Pad8)") (class "Default")
      (node (ref "J2") (pin "8") (pinfunction "NC/TDI_8") (pintype "bidirectional"))
    )
    (net (code "77") (name "unconnected-(J2-SWO{slash}TDO-Pad6)") (class "Default")
      (node (ref "J2") (pin "6") (pinfunction "SWO/TDO_6") (pintype "bidirectional"))
    )
    (net (code "78") (name "unconnected-(SW1-Pad1)") (class "Default")
      (node (ref "SW1") (pin "1") (pinfunction "1_1") (pintype "bidirectional"))
    )
    (net (code "79") (name "unconnected-(SW1-Pad5)") (class "Default")
      (node (ref "SW1") (pin "5") (pinfunction "5_5") (pintype "bidirectional"))
    )
    (net (code "80") (name "unconnected-(SW1-Pad6)") (class "Default")
      (node (ref "SW1") (pin "6") (pinfunction "6_6") (pintype "bidirectional"))
    )
    (net (code "81") (name "unconnected-(SW1-Pad7)") (class "Default")
      (node (ref "SW1") (pin "7") (pinfunction "7_7") (pintype "bidirectional"))
    )
    (net (code "82") (name "unconnected-(U3-D2{slash}I2C_SDA-Pad20)") (class "Default")
      (node (ref "U3") (pin "20") (pinfunction "D2/I2C_SDA_20") (pintype "bidirectional"))
    )
    (net (code "83") (name "unconnected-(U3-D3-Pad21)") (class "Default")
      (node (ref "U3") (pin "21") (pinfunction "D3_21") (pintype "bidirectional"))
    )
    (net (code "84") (name "unconnected-(U3-D4-Pad22)") (class "Default")
      (node (ref "U3") (pin "22") (pinfunction "D4_22") (pintype "bidirectional"))
    )
    (net (code "85") (name "unconnected-(U3-D5-Pad23)") (class "Default")
      (node (ref "U3") (pin "23") (pinfunction "D5_23") (pintype "bidirectional"))
    )
    (net (code "86") (name "unconnected-(U3-D6-Pad24)") (class "Default")
      (node (ref "U3") (pin "24") (pinfunction "D6_24") (pintype "bidirectional"))
    )
    (net (code "87") (name "unconnected-(U3-D7-Pad25)") (class "Default")
      (node (ref "U3") (pin "25") (pinfunction "D7_25") (pintype "bidirectional"))
    )
    (net (code "88") (name "unconnected-(U3-E{slash}RD-Pad17)") (class "Default")
      (node (ref "U3") (pin "17") (pinfunction "E/RD_17") (pintype "input"))
    )
    (net (code "89") (name "unconnected-(U3-NC-Pad7)") (class "Default")
      (node (ref "U3") (pin "7") (pinfunction "NC_7") (pintype "no_connect"))
    )
    (net (code "90") (name "unconnected-(U3-R{slash}W-Pad16)") (class "Default")
      (node (ref "U3") (pin "16") (pinfunction "R/W_16") (pintype "input"))
    )
    (net (code "91") (name "unconnected-(USB1-ID-Pad4)") (class "Default")
      (node (ref "USB1") (pin "4") (pinfunction "ID_4") (pintype "bidirectional"))
    )
  )
)
